# SOM_Power.net
KiCad netlist of a schematic drawn in Altium Designer
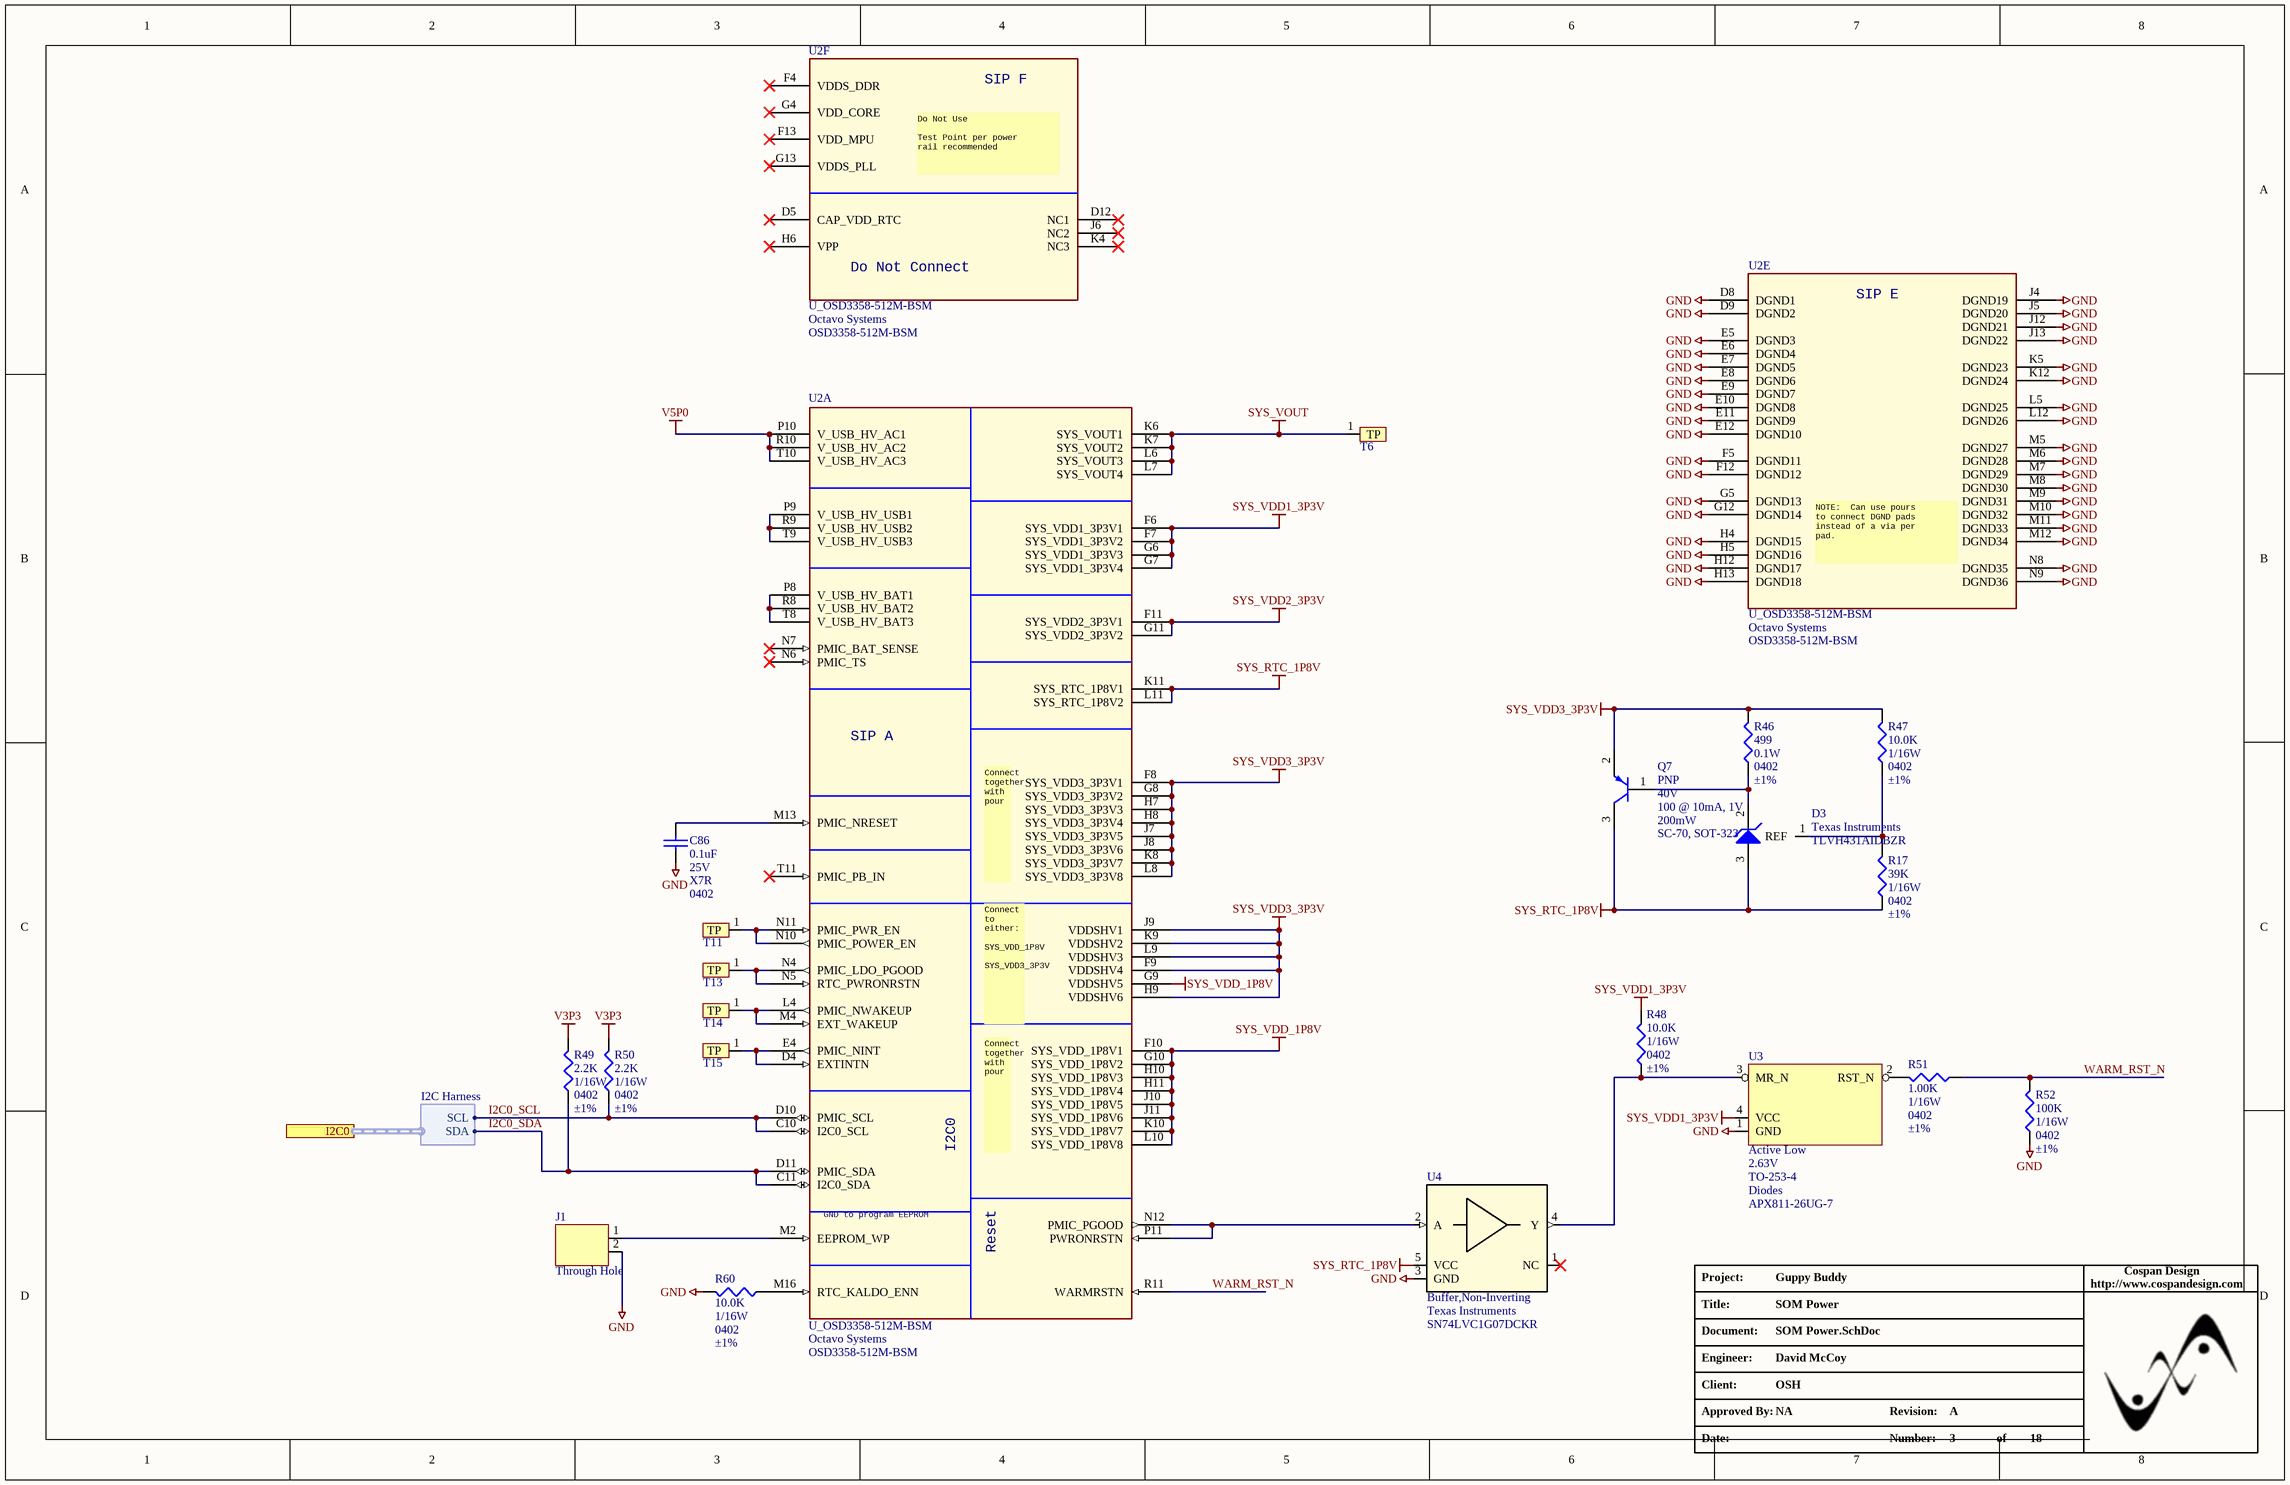
[diagram p0: SOM Power.SchDoc]

(export (version "E")
  (design (tool "Eeschema 10.0.6"))
  (components
    (comp (ref "C86")
      (value "C_0402_0.1UF_25V")
      (footprint "C_0402")
      (description "CAP CER 0.1UF 25V X6S 0402")
      (fields
        (field (name "TOLERANCE") "10%")
        (field (name "CAPACITANCE") "0.1uF")
        (field (name "VOLTAGE - RATED") "25V")
        (field (name "TEMPERATURE COEFFICIENT") "X7R")
        (field (name "PACKAGE / CASE") "0402")
      )
      (libsource (lib "Cospan Design") (part "C_0402_0.1UF_25V"))
    )
    (comp (ref "D3")
      (value "D_TLVH431AIDBZR")
      (footprint "SOT23")
      (description "IC VREF SHUNT ADJ SOT23-3")
      (fields
        (field (name "MANUFACTURER_PART_NUMBER") "TLVH431AIDBZR")
        (field (name "MANUFACTURER") "Texas Instruments")
        (field (name "MANUFACTURER 1") "Texas Instruments")
        (field (name "MANUFACTURER PART NUMBER 1") "TLVH431AIDBZR")
      )
      (libsource (lib "Cospan Design") (part "D_TLVH431AIDBZR"))
    )
    (comp (ref "J1")
      (value "J_HDR1X2_JUMPER")
      (footprint "HDR_1X2")
      (description "CONN HEADER .100\" 2POS TIN PCB")
      (fields
        (field (name "MANUFACTURER") "Samtec")
        (field (name "MANUFACTURER PART NUMBER") "TSW-102-07-T-S")
        (field (name "MOUNTING TYPE") "Through Hole")
      )
      (libsource (lib "Main Library") (part "J_HDR1X2_JUMPER"))
    )
    (comp (ref "Q7")
      (value "PNP")
      (footprint "SOT-23A")
      (description "TRANS PNP MED PWR 400V SOT23-3")
      (fields
        (field (name "MANUFACTURER") "Diodes Inc")
        (field (name "MANUFACTURER PART NUMBER") "MMST3906-7-F")
        (field (name "TRANSISTOR TYPE") "PNP")
        (field (name "VOLTAGE - COLLECTOR EMITTER BREAKDOWN (MAX)") "40V")
        (field (name "DC CURRENT GAIN (HFE) (MIN) @ IC, VCE") "100 @ 10mA, 1V")
        (field (name "POWER - MAX") "200mW")
        (field (name "PACKAGE / CASE") "SC-70, SOT-323")
      )
      (libsource (lib "Main Library") (part "Q_PNP_200MA"))
    )
    (comp (ref "R17")
      (value "R_0402_39K")
      (footprint "R_0402")
      (description "RES SMD 39K OHM 1% 1/10W 0402")
      (fields
        (field (name "MANUFACTURER") "Panasonic Electronic Components")
        (field (name "MANUFACTURER PART NUMBER") "ERJ-2RKF3902X")
        (field (name "RESISTANCE IN OHMS") "39K")
        (field (name "POWER (WATTS)") "1/16W")
        (field (name "CASE") "0402")
        (field (name "TOLERANCE") "±1%")
      )
      (libsource (lib "Main Library") (part "R_0402_39K"))
    )
    (comp (ref "R46")
      (value "R_0402_499.0")
      (footprint "R_0402")
      (description "RES 499 OHM 1/10W 1% 0402 SMD")
      (fields
        (field (name "MANUFACTURER") "Panasonic - ECG")
        (field (name "MANUFACTURER PART NUMBER") "ERJ-2RKF4990X")
        (field (name "RESISTANCE IN OHMS") "499")
        (field (name "POWER (WATTS)") "0.1W")
        (field (name "CASE") "0402")
        (field (name "TOLERANCE") "±1%")
      )
      (libsource (lib "Main Library") (part "R_0402_499.0"))
    )
    (comp (ref "R47")
      (value "R_0402_10.0K")
      (footprint "R_0402")
      (description "RES 10.0K OHM 1/16W 1% 0402 SMD")
      (fields
        (field (name "MANUFACTURER") "Stackpole Electronics Inc")
        (field (name "MANUFACTURER PART NUMBER") "RMCF0402FT10K0")
        (field (name "RESISTANCE IN OHMS") "10.0K")
        (field (name "POWER (WATTS)") "1/16W")
        (field (name "CASE") "0402")
        (field (name "TOLERANCE") "±1%")
      )
      (libsource (lib "Main Library") (part "R_0402_10.0K"))
    )
    (comp (ref "R48")
      (value "R_0402_10.0K")
      (footprint "R_0402")
      (description "RES 10.0K OHM 1/16W 1% 0402 SMD")
      (fields
        (field (name "MANUFACTURER") "Stackpole Electronics Inc")
        (field (name "MANUFACTURER PART NUMBER") "RMCF0402FT10K0")
        (field (name "RESISTANCE IN OHMS") "10.0K")
        (field (name "POWER (WATTS)") "1/16W")
        (field (name "CASE") "0402")
        (field (name "TOLERANCE") "±1%")
      )
      (libsource (lib "Main Library") (part "R_0402_10.0K"))
    )
    (comp (ref "R49")
      (value "R_0402_2.2K")
      (footprint "R_0402")
      (description "RES SMD 2.2K OHM 1% 1/10W 0402")
      (fields
        (field (name "MANUFACTURER") "Panasonic Electronic Components")
        (field (name "MANUFACTURER PART NUMBER") "ERJ-2RKF2201X")
        (field (name "RESISTANCE IN OHMS") "2.2K")
        (field (name "POWER (WATTS)") "1/16W")
        (field (name "CASE") "0402")
        (field (name "TOLERANCE") "±1%")
      )
      (libsource (lib "Cospan Design") (part "R_0402_2.2K"))
    )
    (comp (ref "R50")
      (value "R_0402_2.2K")
      (footprint "R_0402")
      (description "RES SMD 2.2K OHM 1% 1/10W 0402")
      (fields
        (field (name "MANUFACTURER") "Panasonic Electronic Components")
        (field (name "MANUFACTURER PART NUMBER") "ERJ-2RKF2201X")
        (field (name "RESISTANCE IN OHMS") "2.2K")
        (field (name "POWER (WATTS)") "1/16W")
        (field (name "CASE") "0402")
        (field (name "TOLERANCE") "±1%")
      )
      (libsource (lib "Cospan Design") (part "R_0402_2.2K"))
    )
    (comp (ref "R51")
      (value "1.0k Ohms")
      (footprint "R_0402")
      (description "RES 1.00K OHM 1/16W 1% 0402 SMD")
      (fields
        (field (name "MANUFACTURER") "Yageo")
        (field (name "MANUFACTURER PART NUMBER") "RC0402FR-071KL")
        (field (name "RESISTANCE IN OHMS") "1.00K")
        (field (name "POWER (WATTS)") "1/16W")
        (field (name "CASE") "0402")
        (field (name "TOLERANCE") "±1%")
      )
      (libsource (lib "Cospan Design") (part "R_0402_1.0K"))
    )
    (comp (ref "R52")
      (value "R_0402_100K")
      (footprint "R_0402")
      (description "RES SMD 100K OHM 1% 1/16W 0402")
      (fields
        (field (name "MANUFACTURER") "Yageo")
        (field (name "MANUFACTURER PART NUMBER") "RC0402FR-07100KL")
        (field (name "RESISTANCE IN OHMS") "100K")
        (field (name "POWER (WATTS)") "1/16W")
        (field (name "CASE") "0402")
        (field (name "TOLERANCE") "±1%")
      )
      (libsource (lib "Cospan Design") (part "R_0402_100K"))
    )
    (comp (ref "R60")
      (value "R_0402_10.0K")
      (footprint "R_0402")
      (description "RES 10.0K OHM 1/16W 1% 0402 SMD")
      (fields
        (field (name "MANUFACTURER") "Stackpole Electronics Inc")
        (field (name "MANUFACTURER PART NUMBER") "RMCF0402FT10K0")
        (field (name "RESISTANCE IN OHMS") "10.0K")
        (field (name "POWER (WATTS)") "1/16W")
        (field (name "CASE") "0402")
        (field (name "TOLERANCE") "±1%")
      )
      (libsource (lib "Main Library") (part "R_0402_10.0K"))
    )
    (comp (ref "T6")
      (value "TEST_POINT_SMALL")
      (footprint "TestPointSmall")
      (description "OSCILLOSCOPE TEST POINT")
      (libsource (lib "") (part "TEST_POINT_SMALL_1"))
    )
    (comp (ref "T11")
      (value "TEST_POINT_SMALL")
      (footprint "TestPointSmall")
      (description "OSCILLOSCOPE TEST POINT")
      (libsource (lib "Main LibraryX") (part "TEST_POINT_SMALL"))
    )
    (comp (ref "T13")
      (value "TEST_POINT_SMALL")
      (footprint "TestPointSmall")
      (description "OSCILLOSCOPE TEST POINT")
      (libsource (lib "Main LibraryX") (part "TEST_POINT_SMALL"))
    )
    (comp (ref "T14")
      (value "TEST_POINT_SMALL")
      (footprint "TestPointSmall")
      (description "OSCILLOSCOPE TEST POINT")
      (libsource (lib "Main LibraryX") (part "TEST_POINT_SMALL"))
    )
    (comp (ref "T15")
      (value "TEST_POINT_SMALL")
      (footprint "TestPointSmall")
      (description "OSCILLOSCOPE TEST POINT")
      (libsource (lib "Main LibraryX") (part "TEST_POINT_SMALL"))
    )
    (comp (ref "U2")
      (value "U_OSD3358-512M-BSM")
      (footprint "OSD335X-BGA-256")
      (fields
        (field (name "MANUFACTURER 1") "Octavo Systems")
        (field (name "MANUFACTURER PART NUMBER 1") "OSD3358-512M-BSM")
      )
      (libsource (lib "Cospan Design") (part "U_OSD3358-512M-BSM"))
    )
    (comp (ref "U3")
      (value "U_APX811-26UG-7")
      (footprint "SOT190P237X120-4N")
      (description "Processor Supervisor 2.63V 2.5V/3V/3.3V/5V 4-Pin(3+Tab) SOT-143 T/R")
      (fields
        (field (name "RESET") "Active Low")
        (field (name "THRESHOLD VOLTAGE") "2.63V")
        (field (name "CASE/PACKAGE") "TO-253-4")
        (field (name "MANUFACTURER 1") "Diodes")
        (field (name "MANUFACTURER PART NUMBER 1") "APX811-26UG-7")
      )
      (libsource (lib "Cospan Design") (part "U_APX811-26UG-7"))
    )
    (comp (ref "U4")
      (value "U_SN74LVC1G07DCKR")
      (footprint "DCK5")
      (description "IC BUFF/DVR NON-INVERT SC705")
      (fields
        (field (name "LOGIC FUNCTION") "Buffer,Non-Inverting")
        (field (name "MANUFACTURER 1") "Texas Instruments")
        (field (name "MANUFACTURER PART NUMBER 1") "SN74LVC1G07DCKR")
      )
      (libsource (lib "Cospan Design") (part "U_SN74LVC1G07DCKR"))
    )
  )
  (nets
    (net (code "3") (name "/I2C0_SCL") (class "Default")
      (node (ref "R50") (pin "2") (pinfunction "2_2") (pintype "passive"))
      (node (ref "U2") (pin "C10") (pinfunction "I2C0_SCL_C10") (pintype "bidirectional"))
      (node (ref "U2") (pin "D10") (pinfunction "PMIC_SCL_D10") (pintype "bidirectional"))
    )
    (net (code "4") (name "/I2C0_SDA") (class "Default")
      (node (ref "R49") (pin "2") (pinfunction "2_2") (pintype "passive"))
      (node (ref "U2") (pin "C11") (pinfunction "I2C0_SDA_C11") (pintype "bidirectional"))
      (node (ref "U2") (pin "D11") (pinfunction "PMIC_SDA_D11") (pintype "bidirectional"))
    )
    (net (code "5") (name "/WARM_RST_N") (class "Default")
      (node (ref "R51") (pin "2") (pinfunction "2_2") (pintype "passive"))
      (node (ref "R52") (pin "1") (pinfunction "1_1") (pintype "passive"))
      (node (ref "U2") (pin "R11") (pinfunction "WARMRSTN_R11") (pintype "input"))
    )
    (net (code "7") (name "GND") (class "Default")
      (node (ref "C86") (pin "1") (pinfunction "1_1") (pintype "passive"))
      (node (ref "J1") (pin "2") (pinfunction "2_2") (pintype "passive"))
      (node (ref "R52") (pin "2") (pinfunction "2_2") (pintype "passive"))
      (node (ref "R60") (pin "1") (pinfunction "1_1") (pintype "passive"))
      (node (ref "U2") (pin "D8") (pinfunction "DGND1_D8") (pintype "power_in"))
      (node (ref "U2") (pin "D9") (pinfunction "DGND2_D9") (pintype "power_in"))
      (node (ref "U2") (pin "E10") (pinfunction "DGND8_E10") (pintype "power_in"))
      (node (ref "U2") (pin "E11") (pinfunction "DGND9_E11") (pintype "power_in"))
      (node (ref "U2") (pin "E12") (pinfunction "DGND10_E12") (pintype "power_in"))
      (node (ref "U2") (pin "E5") (pinfunction "DGND3_E5") (pintype "power_in"))
      (node (ref "U2") (pin "E6") (pinfunction "DGND4_E6") (pintype "power_in"))
      (node (ref "U2") (pin "E7") (pinfunction "DGND5_E7") (pintype "power_in"))
      (node (ref "U2") (pin "E8") (pinfunction "DGND6_E8") (pintype "power_in"))
      (node (ref "U2") (pin "E9") (pinfunction "DGND7_E9") (pintype "power_in"))
      (node (ref "U2") (pin "F12") (pinfunction "DGND12_F12") (pintype "power_in"))
      (node (ref "U2") (pin "F5") (pinfunction "DGND11_F5") (pintype "power_in"))
      (node (ref "U2") (pin "G12") (pinfunction "DGND14_G12") (pintype "power_in"))
      (node (ref "U2") (pin "G5") (pinfunction "DGND13_G5") (pintype "power_in"))
      (node (ref "U2") (pin "H12") (pinfunction "DGND17_H12") (pintype "power_in"))
      (node (ref "U2") (pin "H13") (pinfunction "DGND18_H13") (pintype "power_in"))
      (node (ref "U2") (pin "H4") (pinfunction "DGND15_H4") (pintype "power_in"))
      (node (ref "U2") (pin "H5") (pinfunction "DGND16_H5") (pintype "power_in"))
      (node (ref "U2") (pin "J12") (pinfunction "DGND21_J12") (pintype "power_in"))
      (node (ref "U2") (pin "J13") (pinfunction "DGND22_J13") (pintype "power_in"))
      (node (ref "U2") (pin "J4") (pinfunction "DGND19_J4") (pintype "power_in"))
      (node (ref "U2") (pin "J5") (pinfunction "DGND20_J5") (pintype "power_in"))
      (node (ref "U2") (pin "K12") (pinfunction "DGND24_K12") (pintype "power_in"))
      (node (ref "U2") (pin "K5") (pinfunction "DGND23_K5") (pintype "power_in"))
      (node (ref "U2") (pin "L12") (pinfunction "DGND26_L12") (pintype "power_in"))
      (node (ref "U2") (pin "L5") (pinfunction "DGND25_L5") (pintype "power_in"))
      (node (ref "U2") (pin "M10") (pinfunction "DGND32_M10") (pintype "power_in"))
      (node (ref "U2") (pin "M11") (pinfunction "DGND33_M11") (pintype "power_in"))
      (node (ref "U2") (pin "M12") (pinfunction "DGND34_M12") (pintype "power_in"))
      (node (ref "U2") (pin "M5") (pinfunction "DGND27_M5") (pintype "power_in"))
      (node (ref "U2") (pin "M6") (pinfunction "DGND28_M6") (pintype "power_in"))
      (node (ref "U2") (pin "M7") (pinfunction "DGND29_M7") (pintype "power_in"))
      (node (ref "U2") (pin "M8") (pinfunction "DGND30_M8") (pintype "power_in"))
      (node (ref "U2") (pin "M9") (pinfunction "DGND31_M9") (pintype "power_in"))
      (node (ref "U2") (pin "N8") (pinfunction "DGND35_N8") (pintype "power_in"))
      (node (ref "U2") (pin "N9") (pinfunction "DGND36_N9") (pintype "power_in"))
      (node (ref "U3") (pin "1") (pinfunction "GND_1") (pintype "passive"))
      (node (ref "U4") (pin "3") (pinfunction "GND_3") (pintype "power_in"))
    )
    (net (code "8") (name "Net-(D3-K)") (class "Default")
      (node (ref "D3") (pin "2") (pinfunction "K_2") (pintype "passive"))
      (node (ref "Q7") (pin "1") (pinfunction "B_1") (pintype "passive"))
      (node (ref "R46") (pin "1") (pinfunction "1_1") (pintype "passive"))
    )
    (net (code "9") (name "Net-(D3-REF)") (class "Default")
      (node (ref "D3") (pin "1") (pinfunction "REF_1") (pintype "passive"))
      (node (ref "R17") (pin "2") (pinfunction "2_2") (pintype "passive"))
      (node (ref "R47") (pin "1") (pinfunction "1_1") (pintype "passive"))
    )
    (net (code "10") (name "Net-(T11-TP)") (class "Default")
      (node (ref "T11") (pin "1") (pinfunction "TP_1") (pintype "passive"))
      (node (ref "U2") (pin "N10") (pinfunction "PMIC_POWER_EN_N10") (pintype "output"))
      (node (ref "U2") (pin "N11") (pinfunction "PMIC_PWR_EN_N11") (pintype "input"))
    )
    (net (code "11") (name "Net-(T13-TP)") (class "Default")
      (node (ref "T13") (pin "1") (pinfunction "TP_1") (pintype "passive"))
      (node (ref "U2") (pin "N4") (pinfunction "PMIC_LDO_PGOOD_N4") (pintype "output"))
      (node (ref "U2") (pin "N5") (pinfunction "RTC_PWRONRSTN_N5") (pintype "input"))
    )
    (net (code "12") (name "Net-(T14-TP)") (class "Default")
      (node (ref "T14") (pin "1") (pinfunction "TP_1") (pintype "passive"))
      (node (ref "U2") (pin "L4") (pinfunction "PMIC_NWAKEUP_L4") (pintype "output"))
      (node (ref "U2") (pin "M4") (pinfunction "EXT_WAKEUP_M4") (pintype "input"))
    )
    (net (code "13") (name "Net-(T15-TP)") (class "Default")
      (node (ref "T15") (pin "1") (pinfunction "TP_1") (pintype "passive"))
      (node (ref "U2") (pin "D4") (pinfunction "EXTINTN_D4") (pintype "input"))
      (node (ref "U2") (pin "E4") (pinfunction "PMIC_NINT_E4") (pintype "output"))
    )
    (net (code "14") (name "Net-(U2A-EEPROM_WP)") (class "Default")
      (node (ref "J1") (pin "1") (pinfunction "1_1") (pintype "passive"))
      (node (ref "U2") (pin "M2") (pinfunction "EEPROM_WP_M2") (pintype "input"))
    )
    (net (code "15") (name "Net-(U2A-PMIC_NRESET)") (class "Default")
      (node (ref "C86") (pin "2") (pinfunction "2_2") (pintype "passive"))
      (node (ref "U2") (pin "M13") (pinfunction "PMIC_NRESET_M13") (pintype "input"))
    )
    (net (code "16") (name "Net-(U2A-PMIC_PGOOD)") (class "Default")
      (node (ref "U2") (pin "N12") (pinfunction "PMIC_PGOOD_N12") (pintype "output"))
      (node (ref "U2") (pin "P11") (pinfunction "PWRONRSTN_P11") (pintype "input"))
      (node (ref "U4") (pin "2") (pinfunction "A_2") (pintype "input"))
    )
    (net (code "17") (name "Net-(U2A-RTC_KALDO_ENN)") (class "Default")
      (node (ref "R60") (pin "2") (pinfunction "2_2") (pintype "passive"))
      (node (ref "U2") (pin "M16") (pinfunction "RTC_KALDO_ENN_M16") (pintype "input"))
    )
    (net (code "18") (name "Net-(U2A-VIN_BAT1)") (class "Default")
      (node (ref "U2") (pin "P8") (pinfunction "VIN_BAT1_P8") (pintype "passive"))
      (node (ref "U2") (pin "R8") (pinfunction "VIN_BAT2_R8") (pintype "passive"))
      (node (ref "U2") (pin "T8") (pinfunction "VIN_BAT3_T8") (pintype "passive"))
    )
    (net (code "19") (name "Net-(U2A-VIN_USB1)") (class "Default")
      (node (ref "U2") (pin "P9") (pinfunction "VIN_USB1_P9") (pintype "passive"))
      (node (ref "U2") (pin "R9") (pinfunction "VIN_USB2_R9") (pintype "passive"))
      (node (ref "U2") (pin "T9") (pinfunction "VIN_USB3_T9") (pintype "passive"))
    )
    (net (code "20") (name "Net-(U3-MR_N)") (class "Default")
      (node (ref "R48") (pin "2") (pinfunction "2_2") (pintype "passive"))
      (node (ref "U3") (pin "3") (pinfunction "MR_N_3") (pintype "passive"))
      (node (ref "U4") (pin "4") (pinfunction "Y_4") (pintype "output"))
    )
    (net (code "21") (name "Net-(U3-RST_N)") (class "Default")
      (node (ref "R51") (pin "1") (pinfunction "1_1") (pintype "passive"))
      (node (ref "U3") (pin "2") (pinfunction "RST_N_2") (pintype "passive"))
    )
    (net (code "22") (name "SYS_RTC_1P8V") (class "Default")
      (node (ref "D3") (pin "3") (pinfunction "A_3") (pintype "passive"))
      (node (ref "Q7") (pin "3") (pinfunction "C_3") (pintype "passive"))
      (node (ref "R17") (pin "1") (pinfunction "1_1") (pintype "passive"))
      (node (ref "U2") (pin "K11") (pinfunction "SYS_RTC_1P8V1_K11") (pintype "power_in"))
      (node (ref "U2") (pin "L11") (pinfunction "SYS_RTC_1P8V2_L11") (pintype "power_in"))
      (node (ref "U4") (pin "5") (pinfunction "VCC_5") (pintype "power_in"))
    )
    (net (code "23") (name "SYS_VDD1_3P3V") (class "Default")
      (node (ref "R48") (pin "1") (pinfunction "1_1") (pintype "passive"))
      (node (ref "U2") (pin "F6") (pinfunction "SYS_VDD1_3P3V1_F6") (pintype "power_in"))
      (node (ref "U2") (pin "F7") (pinfunction "SYS_VDD1_3P3V2_F7") (pintype "power_in"))
      (node (ref "U2") (pin "G6") (pinfunction "SYS_VDD1_3P3V3_G6") (pintype "power_in"))
      (node (ref "U2") (pin "G7") (pinfunction "SYS_VDD1_3P3V4_G7") (pintype "power_in"))
      (node (ref "U3") (pin "4") (pinfunction "VCC_4") (pintype "passive"))
    )
    (net (code "24") (name "SYS_VDD2_3P3V") (class "Default")
      (node (ref "U2") (pin "F11") (pinfunction "SYS_VDD2_3P3V1_F11") (pintype "power_in"))
      (node (ref "U2") (pin "G11") (pinfunction "SYS_VDD2_3P3V2_G11") (pintype "power_in"))
    )
    (net (code "25") (name "SYS_VDD3_3P3V") (class "Default")
      (node (ref "Q7") (pin "2") (pinfunction "E_2") (pintype "passive"))
      (node (ref "R46") (pin "2") (pinfunction "2_2") (pintype "passive"))
      (node (ref "R47") (pin "2") (pinfunction "2_2") (pintype "passive"))
      (node (ref "U2") (pin "F8") (pinfunction "SYS_VDD3_3P3V1_F8") (pintype "power_in"))
      (node (ref "U2") (pin "F9") (pinfunction "VDDSHV4_F9") (pintype "power_in"))
      (node (ref "U2") (pin "G8") (pinfunction "SYS_VDD3_3P3V2_G8") (pintype "power_in"))
      (node (ref "U2") (pin "H7") (pinfunction "SYS_VDD3_3P3V3_H7") (pintype "power_in"))
      (node (ref "U2") (pin "H8") (pinfunction "SYS_VDD3_3P3V4_H8") (pintype "power_in"))
      (node (ref "U2") (pin "H9") (pinfunction "VDDSHV6_H9") (pintype "power_in"))
      (node (ref "U2") (pin "J7") (pinfunction "SYS_VDD3_3P3V5_J7") (pintype "power_in"))
      (node (ref "U2") (pin "J8") (pinfunction "SYS_VDD3_3P3V6_J8") (pintype "power_in"))
      (node (ref "U2") (pin "J9") (pinfunction "VDDSHV1_J9") (pintype "power_in"))
      (node (ref "U2") (pin "K8") (pinfunction "SYS_VDD3_3P3V7_K8") (pintype "power_in"))
      (node (ref "U2") (pin "K9") (pinfunction "VDDSHV2_K9") (pintype "power_in"))
      (node (ref "U2") (pin "L8") (pinfunction "SYS_VDD3_3P3V8_L8") (pintype "power_in"))
      (node (ref "U2") (pin "L9") (pinfunction "VDDSHV3_L9") (pintype "power_in"))
    )
    (net (code "26") (name "SYS_VDD_1P8V") (class "Default")
      (node (ref "U2") (pin "F10") (pinfunction "SYS_VDD_1P8V1_F10") (pintype "power_in"))
      (node (ref "U2") (pin "G10") (pinfunction "SYS_VDD_1P8V2_G10") (pintype "power_in"))
      (node (ref "U2") (pin "G9") (pinfunction "VDDSHV5_G9") (pintype "power_in"))
      (node (ref "U2") (pin "H10") (pinfunction "SYS_VDD_1P8V3_H10") (pintype "power_in"))
      (node (ref "U2") (pin "H11") (pinfunction "SYS_VDD_1P8V4_H11") (pintype "power_in"))
      (node (ref "U2") (pin "J10") (pinfunction "SYS_VDD_1P8V5_J10") (pintype "power_in"))
      (node (ref "U2") (pin "J11") (pinfunction "SYS_VDD_1P8V6_J11") (pintype "power_in"))
      (node (ref "U2") (pin "K10") (pinfunction "SYS_VDD_1P8V7_K10") (pintype "power_in"))
      (node (ref "U2") (pin "L10") (pinfunction "SYS_VDD_1P8V8_L10") (pintype "power_in"))
    )
    (net (code "27") (name "SYS_VOUT") (class "Default")
      (node (ref "T6") (pin "1") (pinfunction "TP_1") (pintype "passive"))
      (node (ref "U2") (pin "K6") (pinfunction "SYS_VOUT1_K6") (pintype "power_in"))
      (node (ref "U2") (pin "K7") (pinfunction "SYS_VOUT2_K7") (pintype "power_in"))
      (node (ref "U2") (pin "L6") (pinfunction "SYS_VOUT3_L6") (pintype "power_in"))
      (node (ref "U2") (pin "L7") (pinfunction "SYS_VOUT4_L7") (pintype "power_in"))
    )
    (net (code "28") (name "V3P3") (class "Default")
      (node (ref "R49") (pin "1") (pinfunction "1_1") (pintype "passive"))
      (node (ref "R50") (pin "1") (pinfunction "1_1") (pintype "passive"))
    )
    (net (code "29") (name "V5P0") (class "Default")
      (node (ref "U2") (pin "P10") (pinfunction "VIN_AC1_P10") (pintype "passive"))
      (node (ref "U2") (pin "R10") (pinfunction "VIN_AC2_R10") (pintype "passive"))
      (node (ref "U2") (pin "T10") (pinfunction "VIN_AC3_T10") (pintype "passive"))
    )
    (net (code "30") (name "unconnected-(U2A-PMIC_BAT_SENSE-PadN7)") (class "Default")
      (node (ref "U2") (pin "N7") (pinfunction "PMIC_BAT_SENSE_N7") (pintype "input+no_connect"))
    )
    (net (code "31") (name "unconnected-(U2A-PMIC_PB_IN-PadT11)") (class "Default")
      (node (ref "U2") (pin "T11") (pinfunction "PMIC_PB_IN_T11") (pintype "input+no_connect"))
    )
    (net (code "32") (name "unconnected-(U2A-PMIC_TS-PadN6)") (class "Default")
      (node (ref "U2") (pin "N6") (pinfunction "PMIC_TS_N6") (pintype "input+no_connect"))
    )
    (net (code "33") (name "unconnected-(U2F-CAP_VDD_RTC-PadD5)") (class "Default")
      (node (ref "U2") (pin "D5") (pinfunction "CAP_VDD_RTC_D5") (pintype "power_in+no_connect"))
    )
    (net (code "34") (name "unconnected-(U2F-NC1-PadD12)") (class "Default")
      (node (ref "U2") (pin "D12") (pinfunction "NC1_D12") (pintype "passive+no_connect"))
    )
    (net (code "35") (name "unconnected-(U2F-NC2-PadJ6)") (class "Default")
      (node (ref "U2") (pin "J6") (pinfunction "NC2_J6") (pintype "passive+no_connect"))
    )
    (net (code "36") (name "unconnected-(U2F-NC3-PadK4)") (class "Default")
      (node (ref "U2") (pin "K4") (pinfunction "NC3_K4") (pintype "passive+no_connect"))
    )
    (net (code "37") (name "unconnected-(U2F-VDDS_DDR-PadF4)") (class "Default")
      (node (ref "U2") (pin "F4") (pinfunction "VDDS_DDR_F4") (pintype "power_in+no_connect"))
    )
    (net (code "38") (name "unconnected-(U2F-VDDS_PLL-PadG13)") (class "Default")
      (node (ref "U2") (pin "G13") (pinfunction "VDDS_PLL_G13") (pintype "power_in+no_connect"))
    )
    (net (code "39") (name "unconnected-(U2F-VDD_CORE-PadG4)") (class "Default")
      (node (ref "U2") (pin "G4") (pinfunction "VDD_CORE_G4") (pintype "power_in+no_connect"))
    )
    (net (code "40") (name "unconnected-(U2F-VDD_MPU-PadF13)") (class "Default")
      (node (ref "U2") (pin "F13") (pinfunction "VDD_MPU_F13") (pintype "power_in+no_connect"))
    )
    (net (code "41") (name "unconnected-(U2F-VPP-PadH6)") (class "Default")
      (node (ref "U2") (pin "H6") (pinfunction "VPP_H6") (pintype "power_in+no_connect"))
    )
    (net (code "42") (name "unconnected-(U4-NC-Pad1)") (class "Default")
      (node (ref "U4") (pin "1") (pinfunction "NC_1") (pintype "passive+no_connect"))
    )
  )
)
